# DRIVER.net
KiCad netlist of a schematic drawn in Altium Designer
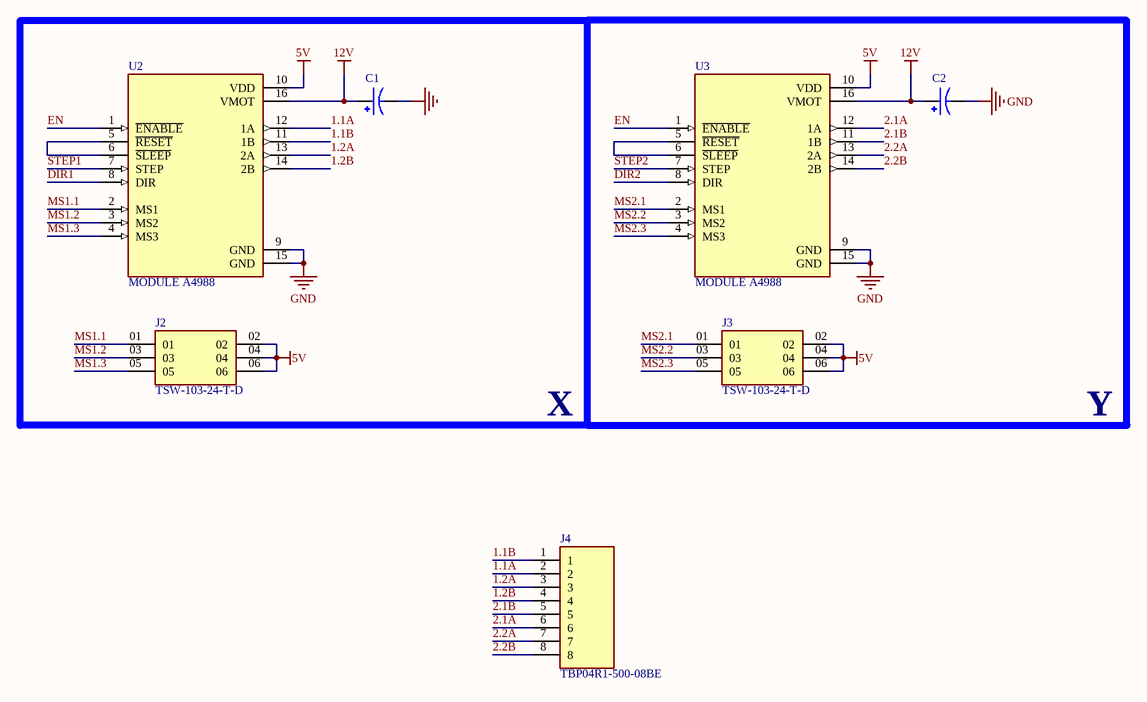
[diagram p0: DRIVER.SchDoc]

(export (version "E")
  (design (tool "Eeschema 10.0.6"))
  (components
    (comp (ref "C1")
      (value "EEUFR1V101B")
      (footprint "EEU-FR1V101B")
      (description "AL LYTIC, RADIAL, 35VDC, 100UF")
      (fields (field (name "MF") "Panasonic"))
      (libsource (lib "CAP") (part "EEUFR1V101B"))
    )
    (comp (ref "C2")
      (value "EEUFR1V101B")
      (footprint "EEU-FR1V101B")
      (description "AL LYTIC, RADIAL, 35VDC, 100UF")
      (fields (field (name "MF") "Panasonic"))
      (libsource (lib "CAP") (part "EEUFR1V101B"))
    )
    (comp (ref "J2")
      (value "TSW-103-24-T-D")
      (footprint "TSW-103-24-T-D")
      (description "TSW - 2.54mm Samtec Pin Header 12.15mm Overall Pin Length (24) - Fast Stock(mcv)")
      (libsource (lib "JUM") (part "TSW-103-24-T-D"))
    )
    (comp (ref "J3")
      (value "TSW-103-24-T-D")
      (footprint "TSW-103-24-T-D")
      (description "TSW - 2.54mm Samtec Pin Header 12.15mm Overall Pin Length (24) - Fast Stock(mcv)")
      (libsource (lib "JUM") (part "TSW-103-24-T-D"))
    )
    (comp (ref "J4")
      (value "TBP04R1-500-08BE")
      (footprint "TBP04R1-500-08BE")
      (description "2~24 Poles, Pluggable, Receptacle, Horizontal, 5.0 Pitch, Terminal Block Connector")
      (fields (field (name "MF") "Same Sky"))
      (libsource (lib "JACK") (part "TBP04R1-500-08BE"))
    )
    (comp (ref "U2")
      (value "MODULE A4988")
      (footprint "MODULE A4988")
      (description "Stepper motor controler; IC: A4988; 1A; Uin mot: 8Ã·35V")
      (fields (field (name "MP") "A4988_STEPPER_MOTOR_DRIVER_CARRIER"))
      (libsource (lib "MODULE") (part "MODULE A4988"))
    )
    (comp (ref "U3")
      (value "MODULE A4988")
      (footprint "MODULE A4988")
      (description "Stepper motor controler; IC: A4988; 1A; Uin mot: 8Ã·35V")
      (fields (field (name "MP") "A4988_STEPPER_MOTOR_DRIVER_CARRIER"))
      (libsource (lib "MODULE") (part "MODULE A4988"))
    )
  )
  (nets
    (net (code "1") (name "/1.1A") (class "Default")
      (node (ref "J4") (pin "2") (pinfunction "2_2") (pintype "passive"))
      (node (ref "U2") (pin "12") (pinfunction "1A_12") (pintype "output"))
    )
    (net (code "2") (name "/1.1B") (class "Default")
      (node (ref "J4") (pin "1") (pinfunction "1_1") (pintype "passive"))
      (node (ref "U2") (pin "11") (pinfunction "1B_11") (pintype "output"))
    )
    (net (code "3") (name "/1.2A") (class "Default")
      (node (ref "J4") (pin "3") (pinfunction "3_3") (pintype "passive"))
      (node (ref "U2") (pin "13") (pinfunction "2A_13") (pintype "output"))
    )
    (net (code "4") (name "/1.2B") (class "Default")
      (node (ref "J4") (pin "4") (pinfunction "4_4") (pintype "passive"))
      (node (ref "U2") (pin "14") (pinfunction "2B_14") (pintype "output"))
    )
    (net (code "5") (name "/2.1A") (class "Default")
      (node (ref "J4") (pin "6") (pinfunction "6_6") (pintype "passive"))
      (node (ref "U3") (pin "12") (pinfunction "1A_12") (pintype "output"))
    )
    (net (code "6") (name "/2.1B") (class "Default")
      (node (ref "J4") (pin "5") (pinfunction "5_5") (pintype "passive"))
      (node (ref "U3") (pin "11") (pinfunction "1B_11") (pintype "output"))
    )
    (net (code "7") (name "/2.2A") (class "Default")
      (node (ref "J4") (pin "7") (pinfunction "7_7") (pintype "passive"))
      (node (ref "U3") (pin "13") (pinfunction "2A_13") (pintype "output"))
    )
    (net (code "8") (name "/2.2B") (class "Default")
      (node (ref "J4") (pin "8") (pinfunction "8_8") (pintype "passive"))
      (node (ref "U3") (pin "14") (pinfunction "2B_14") (pintype "output"))
    )
    (net (code "9") (name "/DIR1") (class "Default")
      (node (ref "U2") (pin "8") (pinfunction "DIR_8") (pintype "input"))
    )
    (net (code "10") (name "/DIR2") (class "Default")
      (node (ref "U3") (pin "8") (pinfunction "DIR_8") (pintype "input"))
    )
    (net (code "11") (name "/EN") (class "Default")
      (node (ref "U2") (pin "1") (pinfunction "~{ENABLE}_1") (pintype "input"))
      (node (ref "U3") (pin "1") (pinfunction "~{ENABLE}_1") (pintype "input"))
    )
    (net (code "12") (name "/MS1.1") (class "Default")
      (node (ref "J2") (pin "01") (pinfunction "01_01") (pintype "passive"))
      (node (ref "U2") (pin "2") (pinfunction "MS1_2") (pintype "input"))
    )
    (net (code "13") (name "/MS1.2") (class "Default")
      (node (ref "J2") (pin "03") (pinfunction "03_03") (pintype "passive"))
      (node (ref "U2") (pin "3") (pinfunction "MS2_3") (pintype "input"))
    )
    (net (code "14") (name "/MS1.3") (class "Default")
      (node (ref "J2") (pin "05") (pinfunction "05_05") (pintype "passive"))
      (node (ref "U2") (pin "4") (pinfunction "MS3_4") (pintype "input"))
    )
    (net (code "15") (name "/MS2.1") (class "Default")
      (node (ref "J3") (pin "01") (pinfunction "01_01") (pintype "passive"))
      (node (ref "U3") (pin "2") (pinfunction "MS1_2") (pintype "input"))
    )
    (net (code "16") (name "/MS2.2") (class "Default")
      (node (ref "J3") (pin "03") (pinfunction "03_03") (pintype "passive"))
      (node (ref "U3") (pin "3") (pinfunction "MS2_3") (pintype "input"))
    )
    (net (code "17") (name "/MS2.3") (class "Default")
      (node (ref "J3") (pin "05") (pinfunction "05_05") (pintype "passive"))
      (node (ref "U3") (pin "4") (pinfunction "MS3_4") (pintype "input"))
    )
    (net (code "18") (name "/STEP1") (class "Default")
      (node (ref "U2") (pin "7") (pinfunction "STEP_7") (pintype "input"))
    )
    (net (code "19") (name "/STEP2") (class "Default")
      (node (ref "U3") (pin "7") (pinfunction "STEP_7") (pintype "input"))
    )
    (net (code "20") (name "5V") (class "Default")
      (node (ref "J2") (pin "02") (pinfunction "02_02") (pintype "passive"))
      (node (ref "J2") (pin "04") (pinfunction "04_04") (pintype "passive"))
      (node (ref "J2") (pin "06") (pinfunction "06_06") (pintype "passive"))
      (node (ref "J3") (pin "02") (pinfunction "02_02") (pintype "passive"))
      (node (ref "J3") (pin "04") (pinfunction "04_04") (pintype "passive"))
      (node (ref "J3") (pin "06") (pinfunction "06_06") (pintype "passive"))
      (node (ref "U2") (pin "10") (pinfunction "VDD_10") (pintype "power_in"))
      (node (ref "U3") (pin "10") (pinfunction "VDD_10") (pintype "power_in"))
    )
    (net (code "21") (name "12V") (class "Default")
      (node (ref "C1") (pin "P") (pinfunction "P_P") (pintype "passive"))
      (node (ref "C2") (pin "P") (pinfunction "P_P") (pintype "passive"))
      (node (ref "U2") (pin "16") (pinfunction "VMOT_16") (pintype "power_in"))
      (node (ref "U3") (pin "16") (pinfunction "VMOT_16") (pintype "power_in"))
    )
    (net (code "22") (name "GND") (class "Default")
      (node (ref "C1") (pin "N") (pinfunction "N_N") (pintype "passive"))
      (node (ref "C2") (pin "N") (pinfunction "N_N") (pintype "passive"))
      (node (ref "U2") (pin "15") (pinfunction "GND_15") (pintype "power_in"))
      (node (ref "U2") (pin "9") (pinfunction "GND_9") (pintype "power_in"))
      (node (ref "U3") (pin "15") (pinfunction "GND_15") (pintype "power_in"))
      (node (ref "U3") (pin "9") (pinfunction "GND_9") (pintype "power_in"))
    )
    (net (code "23") (name "Net-(U2-~{RESET})") (class "Default")
      (node (ref "U2") (pin "5") (pinfunction "~{RESET}_5") (pintype "passive"))
      (node (ref "U2") (pin "6") (pinfunction "~{SLEEP}_6") (pintype "passive"))
    )
    (net (code "24") (name "Net-(U3-~{RESET})") (class "Default")
      (node (ref "U3") (pin "5") (pinfunction "~{RESET}_5") (pintype "passive"))
      (node (ref "U3") (pin "6") (pinfunction "~{SLEEP}_6") (pintype "passive"))
    )
  )
)
